# ESC-Player_BackBoardV03.net
KiCad netlist of a schematic drawn in EasyEDA Pro
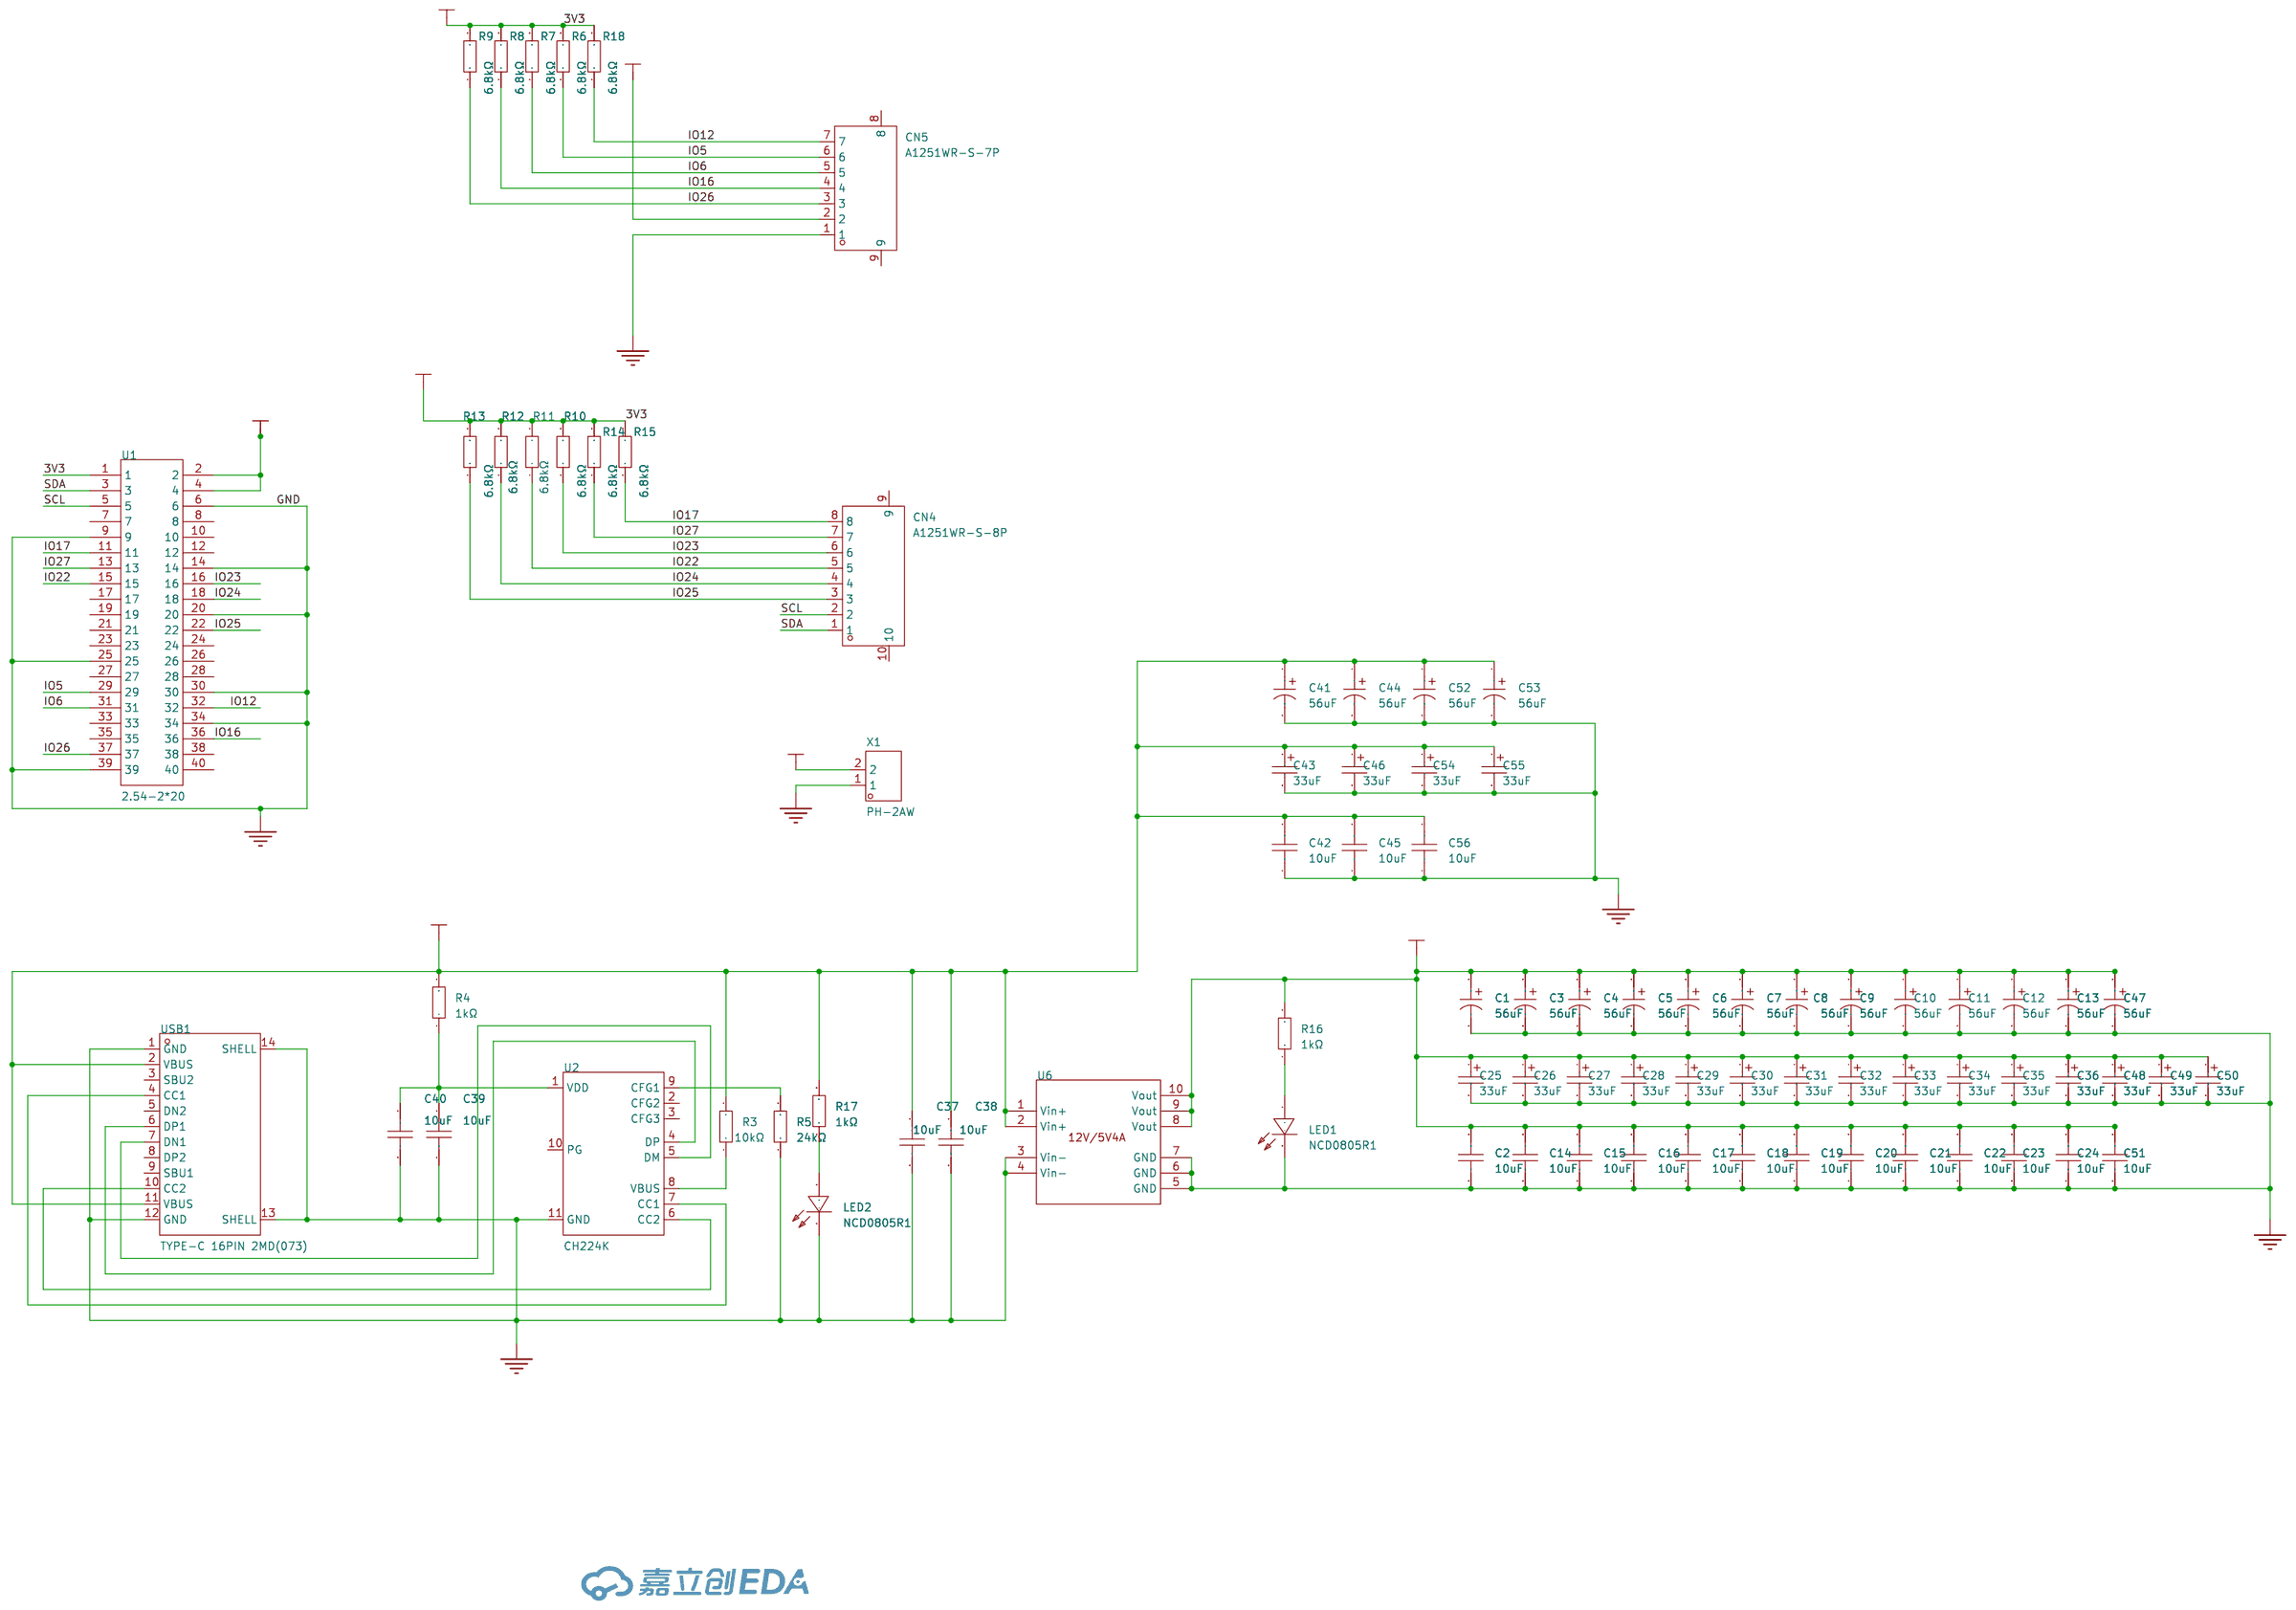
[diagram p0: schematic sheet]

(export (version "E")
  (design (tool "Eeschema 10.0.6"))
  (components
    (comp (ref "C1")
      (value "56uF")
      (footprint "easyedapro:CAP-SMD_BD6.3-L6.6-W6.6-LS7.2-FD")
      (description "容值:56uF;精度:±20%;额定电压:25V;")
      (fields (field (name "Manufacturer Part") "HBW560M1ETR-0606") (field (name "Manufacturer") "lelon(立隆)"))
      (libsource (lib "easyedapro") (part "HBW560M1ETR-0606"))
    )
    (comp (ref "C2")
      (value "10uF")
      (footprint "easyedapro:C1206")
      (description "容值:10uF;精度:±10%;额定电压:50V;材质(温度系数):X5R;")
      (fields
        (field (name "Manufacturer Part") "HGC1206R5106K500NSPJ")
        (field (name "Manufacturer") "Chinocera(华瓷)")
      )
      (libsource (lib "easyedapro") (part "HGC1206R5106K500NSPJ"))
    )
    (comp (ref "C3")
      (value "56uF")
      (footprint "easyedapro:CAP-SMD_BD6.3-L6.6-W6.6-LS7.2-FD")
      (description "容值:56uF;精度:±20%;额定电压:25V;")
      (fields (field (name "Manufacturer Part") "HBW560M1ETR-0606") (field (name "Manufacturer") "lelon(立隆)"))
      (libsource (lib "easyedapro") (part "HBW560M1ETR-0606"))
    )
    (comp (ref "C4")
      (value "56uF")
      (footprint "easyedapro:CAP-SMD_BD6.3-L6.6-W6.6-LS7.2-FD")
      (description "容值:56uF;精度:±20%;额定电压:25V;")
      (fields (field (name "Manufacturer Part") "HBW560M1ETR-0606") (field (name "Manufacturer") "lelon(立隆)"))
      (libsource (lib "easyedapro") (part "HBW560M1ETR-0606"))
    )
    (comp (ref "C5")
      (value "56uF")
      (footprint "easyedapro:CAP-SMD_BD6.3-L6.6-W6.6-LS7.2-FD")
      (description "容值:56uF;精度:±20%;额定电压:25V;")
      (fields (field (name "Manufacturer Part") "HBW560M1ETR-0606") (field (name "Manufacturer") "lelon(立隆)"))
      (libsource (lib "easyedapro") (part "HBW560M1ETR-0606"))
    )
    (comp (ref "C6")
      (value "56uF")
      (footprint "easyedapro:CAP-SMD_BD6.3-L6.6-W6.6-LS7.2-FD")
      (description "容值:56uF;精度:±20%;额定电压:25V;")
      (fields (field (name "Manufacturer Part") "HBW560M1ETR-0606") (field (name "Manufacturer") "lelon(立隆)"))
      (libsource (lib "easyedapro") (part "HBW560M1ETR-0606"))
    )
    (comp (ref "C7")
      (value "56uF")
      (footprint "easyedapro:CAP-SMD_BD6.3-L6.6-W6.6-LS7.2-FD")
      (description "容值:56uF;精度:±20%;额定电压:25V;")
      (fields (field (name "Manufacturer Part") "HBW560M1ETR-0606") (field (name "Manufacturer") "lelon(立隆)"))
      (libsource (lib "easyedapro") (part "HBW560M1ETR-0606"))
    )
    (comp (ref "C8")
      (value "56uF")
      (footprint "easyedapro:CAP-SMD_BD6.3-L6.6-W6.6-LS7.2-FD")
      (description "容值:56uF;精度:±20%;额定电压:25V;")
      (fields (field (name "Manufacturer Part") "HBW560M1ETR-0606") (field (name "Manufacturer") "lelon(立隆)"))
      (libsource (lib "easyedapro") (part "HBW560M1ETR-0606"))
    )
    (comp (ref "C9")
      (value "56uF")
      (footprint "easyedapro:CAP-SMD_BD6.3-L6.6-W6.6-LS7.2-FD")
      (description "容值:56uF;精度:±20%;额定电压:25V;")
      (fields (field (name "Manufacturer Part") "HBW560M1ETR-0606") (field (name "Manufacturer") "lelon(立隆)"))
      (libsource (lib "easyedapro") (part "HBW560M1ETR-0606"))
    )
    (comp (ref "C10")
      (value "56uF")
      (footprint "easyedapro:CAP-SMD_BD6.3-L6.6-W6.6-LS7.2-FD")
      (description "容值:56uF;精度:±20%;额定电压:25V;")
      (fields (field (name "Manufacturer Part") "HBW560M1ETR-0606") (field (name "Manufacturer") "lelon(立隆)"))
      (libsource (lib "easyedapro") (part "HBW560M1ETR-0606"))
    )
    (comp (ref "C11")
      (value "56uF")
      (footprint "easyedapro:CAP-SMD_BD6.3-L6.6-W6.6-LS7.2-FD")
      (description "容值:56uF;精度:±20%;额定电压:25V;")
      (fields (field (name "Manufacturer Part") "HBW560M1ETR-0606") (field (name "Manufacturer") "lelon(立隆)"))
      (libsource (lib "easyedapro") (part "HBW560M1ETR-0606"))
    )
    (comp (ref "C12")
      (value "56uF")
      (footprint "easyedapro:CAP-SMD_BD6.3-L6.6-W6.6-LS7.2-FD")
      (description "容值:56uF;精度:±20%;额定电压:25V;")
      (fields (field (name "Manufacturer Part") "HBW560M1ETR-0606") (field (name "Manufacturer") "lelon(立隆)"))
      (libsource (lib "easyedapro") (part "HBW560M1ETR-0606"))
    )
    (comp (ref "C13")
      (value "56uF")
      (footprint "easyedapro:CAP-SMD_BD6.3-L6.6-W6.6-LS7.2-FD")
      (description "容值:56uF;精度:±20%;额定电压:25V;")
      (fields (field (name "Manufacturer Part") "HBW560M1ETR-0606") (field (name "Manufacturer") "lelon(立隆)"))
      (libsource (lib "easyedapro") (part "HBW560M1ETR-0606"))
    )
    (comp (ref "C14")
      (value "10uF")
      (footprint "easyedapro:C1206")
      (description "容值:10uF;精度:±10%;额定电压:50V;材质(温度系数):X5R;")
      (fields
        (field (name "Manufacturer Part") "HGC1206R5106K500NSPJ")
        (field (name "Manufacturer") "Chinocera(华瓷)")
      )
      (libsource (lib "easyedapro") (part "HGC1206R5106K500NSPJ"))
    )
    (comp (ref "C15")
      (value "10uF")
      (footprint "easyedapro:C1206")
      (description "容值:10uF;精度:±10%;额定电压:50V;材质(温度系数):X5R;")
      (fields
        (field (name "Manufacturer Part") "HGC1206R5106K500NSPJ")
        (field (name "Manufacturer") "Chinocera(华瓷)")
      )
      (libsource (lib "easyedapro") (part "HGC1206R5106K500NSPJ"))
    )
    (comp (ref "C16")
      (value "10uF")
      (footprint "easyedapro:C1206")
      (description "容值:10uF;精度:±10%;额定电压:50V;材质(温度系数):X5R;")
      (fields
        (field (name "Manufacturer Part") "HGC1206R5106K500NSPJ")
        (field (name "Manufacturer") "Chinocera(华瓷)")
      )
      (libsource (lib "easyedapro") (part "HGC1206R5106K500NSPJ"))
    )
    (comp (ref "C17")
      (value "10uF")
      (footprint "easyedapro:C1206")
      (description "容值:10uF;精度:±10%;额定电压:50V;材质(温度系数):X5R;")
      (fields
        (field (name "Manufacturer Part") "HGC1206R5106K500NSPJ")
        (field (name "Manufacturer") "Chinocera(华瓷)")
      )
      (libsource (lib "easyedapro") (part "HGC1206R5106K500NSPJ"))
    )
    (comp (ref "C18")
      (value "10uF")
      (footprint "easyedapro:C1206")
      (description "容值:10uF;精度:±10%;额定电压:50V;材质(温度系数):X5R;")
      (fields
        (field (name "Manufacturer Part") "HGC1206R5106K500NSPJ")
        (field (name "Manufacturer") "Chinocera(华瓷)")
      )
      (libsource (lib "easyedapro") (part "HGC1206R5106K500NSPJ"))
    )
    (comp (ref "C19")
      (value "10uF")
      (footprint "easyedapro:C1206")
      (description "容值:10uF;精度:±10%;额定电压:50V;材质(温度系数):X5R;")
      (fields
        (field (name "Manufacturer Part") "HGC1206R5106K500NSPJ")
        (field (name "Manufacturer") "Chinocera(华瓷)")
      )
      (libsource (lib "easyedapro") (part "HGC1206R5106K500NSPJ"))
    )
    (comp (ref "C20")
      (value "10uF")
      (footprint "easyedapro:C1206")
      (description "容值:10uF;精度:±10%;额定电压:50V;材质(温度系数):X5R;")
      (fields
        (field (name "Manufacturer Part") "HGC1206R5106K500NSPJ")
        (field (name "Manufacturer") "Chinocera(华瓷)")
      )
      (libsource (lib "easyedapro") (part "HGC1206R5106K500NSPJ"))
    )
    (comp (ref "C21")
      (value "10uF")
      (footprint "easyedapro:C1206")
      (description "容值:10uF;精度:±10%;额定电压:50V;材质(温度系数):X5R;")
      (fields
        (field (name "Manufacturer Part") "HGC1206R5106K500NSPJ")
        (field (name "Manufacturer") "Chinocera(华瓷)")
      )
      (libsource (lib "easyedapro") (part "HGC1206R5106K500NSPJ"))
    )
    (comp (ref "C22")
      (value "10uF")
      (footprint "easyedapro:C1206")
      (description "容值:10uF;精度:±10%;额定电压:50V;材质(温度系数):X5R;")
      (fields
        (field (name "Manufacturer Part") "HGC1206R5106K500NSPJ")
        (field (name "Manufacturer") "Chinocera(华瓷)")
      )
      (libsource (lib "easyedapro") (part "HGC1206R5106K500NSPJ"))
    )
    (comp (ref "C23")
      (value "10uF")
      (footprint "easyedapro:C1206")
      (description "容值:10uF;精度:±10%;额定电压:50V;材质(温度系数):X5R;")
      (fields
        (field (name "Manufacturer Part") "HGC1206R5106K500NSPJ")
        (field (name "Manufacturer") "Chinocera(华瓷)")
      )
      (libsource (lib "easyedapro") (part "HGC1206R5106K500NSPJ"))
    )
    (comp (ref "C24")
      (value "10uF")
      (footprint "easyedapro:C1206")
      (description "容值:10uF;精度:±10%;额定电压:50V;材质(温度系数):X5R;")
      (fields
        (field (name "Manufacturer Part") "HGC1206R5106K500NSPJ")
        (field (name "Manufacturer") "Chinocera(华瓷)")
      )
      (libsource (lib "easyedapro") (part "HGC1206R5106K500NSPJ"))
    )
    (comp (ref "C25")
      (value "33uF")
      (footprint "easyedapro:CAP-SMD_L3.5-W2.8-R-RD")
      (description "容值:33uF;精度:±10%;额定电压:16V;等效串联电阻:2.1Ω@100kHz;")
      (fields (field (name "Manufacturer Part") "TAJB336K016RNJ") (field (name "Manufacturer") "Kyocera AVX"))
      (libsource (lib "easyedapro") (part "TAJB336K016RNJ"))
    )
    (comp (ref "C26")
      (value "33uF")
      (footprint "easyedapro:CAP-SMD_L3.5-W2.8-R-RD")
      (description "容值:33uF;精度:±10%;额定电压:16V;等效串联电阻:2.1Ω@100kHz;")
      (fields (field (name "Manufacturer Part") "TAJB336K016RNJ") (field (name "Manufacturer") "Kyocera AVX"))
      (libsource (lib "easyedapro") (part "TAJB336K016RNJ"))
    )
    (comp (ref "C27")
      (value "33uF")
      (footprint "easyedapro:CAP-SMD_L3.5-W2.8-R-RD")
      (description "容值:33uF;精度:±10%;额定电压:16V;等效串联电阻:2.1Ω@100kHz;")
      (fields (field (name "Manufacturer Part") "TAJB336K016RNJ") (field (name "Manufacturer") "Kyocera AVX"))
      (libsource (lib "easyedapro") (part "TAJB336K016RNJ"))
    )
    (comp (ref "C28")
      (value "33uF")
      (footprint "easyedapro:CAP-SMD_L3.5-W2.8-R-RD")
      (description "容值:33uF;精度:±10%;额定电压:16V;等效串联电阻:2.1Ω@100kHz;")
      (fields (field (name "Manufacturer Part") "TAJB336K016RNJ") (field (name "Manufacturer") "Kyocera AVX"))
      (libsource (lib "easyedapro") (part "TAJB336K016RNJ"))
    )
    (comp (ref "C29")
      (value "33uF")
      (footprint "easyedapro:CAP-SMD_L3.5-W2.8-R-RD")
      (description "容值:33uF;精度:±10%;额定电压:16V;等效串联电阻:2.1Ω@100kHz;")
      (fields (field (name "Manufacturer Part") "TAJB336K016RNJ") (field (name "Manufacturer") "Kyocera AVX"))
      (libsource (lib "easyedapro") (part "TAJB336K016RNJ"))
    )
    (comp (ref "C30")
      (value "33uF")
      (footprint "easyedapro:CAP-SMD_L3.5-W2.8-R-RD")
      (description "容值:33uF;精度:±10%;额定电压:16V;等效串联电阻:2.1Ω@100kHz;")
      (fields (field (name "Manufacturer Part") "TAJB336K016RNJ") (field (name "Manufacturer") "Kyocera AVX"))
      (libsource (lib "easyedapro") (part "TAJB336K016RNJ"))
    )
    (comp (ref "C31")
      (value "33uF")
      (footprint "easyedapro:CAP-SMD_L3.5-W2.8-R-RD")
      (description "容值:33uF;精度:±10%;额定电压:16V;等效串联电阻:2.1Ω@100kHz;")
      (fields (field (name "Manufacturer Part") "TAJB336K016RNJ") (field (name "Manufacturer") "Kyocera AVX"))
      (libsource (lib "easyedapro") (part "TAJB336K016RNJ"))
    )
    (comp (ref "C32")
      (value "33uF")
      (footprint "easyedapro:CAP-SMD_L3.5-W2.8-R-RD")
      (description "容值:33uF;精度:±10%;额定电压:16V;等效串联电阻:2.1Ω@100kHz;")
      (fields (field (name "Manufacturer Part") "TAJB336K016RNJ") (field (name "Manufacturer") "Kyocera AVX"))
      (libsource (lib "easyedapro") (part "TAJB336K016RNJ"))
    )
    (comp (ref "C33")
      (value "33uF")
      (footprint "easyedapro:CAP-SMD_L3.5-W2.8-R-RD")
      (description "容值:33uF;精度:±10%;额定电压:16V;等效串联电阻:2.1Ω@100kHz;")
      (fields (field (name "Manufacturer Part") "TAJB336K016RNJ") (field (name "Manufacturer") "Kyocera AVX"))
      (libsource (lib "easyedapro") (part "TAJB336K016RNJ"))
    )
    (comp (ref "C34")
      (value "33uF")
      (footprint "easyedapro:CAP-SMD_L3.5-W2.8-R-RD")
      (description "容值:33uF;精度:±10%;额定电压:16V;等效串联电阻:2.1Ω@100kHz;")
      (fields (field (name "Manufacturer Part") "TAJB336K016RNJ") (field (name "Manufacturer") "Kyocera AVX"))
      (libsource (lib "easyedapro") (part "TAJB336K016RNJ"))
    )
    (comp (ref "C35")
      (value "33uF")
      (footprint "easyedapro:CAP-SMD_L3.5-W2.8-R-RD")
      (description "容值:33uF;精度:±10%;额定电压:16V;等效串联电阻:2.1Ω@100kHz;")
      (fields (field (name "Manufacturer Part") "TAJB336K016RNJ") (field (name "Manufacturer") "Kyocera AVX"))
      (libsource (lib "easyedapro") (part "TAJB336K016RNJ"))
    )
    (comp (ref "C36")
      (value "33uF")
      (footprint "easyedapro:CAP-SMD_L3.5-W2.8-R-RD")
      (description "容值:33uF;精度:±10%;额定电压:16V;等效串联电阻:2.1Ω@100kHz;")
      (fields (field (name "Manufacturer Part") "TAJB336K016RNJ") (field (name "Manufacturer") "Kyocera AVX"))
      (libsource (lib "easyedapro") (part "TAJB336K016RNJ"))
    )
    (comp (ref "C37")
      (value "10uF")
      (footprint "easyedapro:C0805")
      (description "温度系数:X5R;额定电压:6.3V;精度:±10%;容值:10uF;")
      (fields
        (field (name "Manufacturer Part") "CL21A106KQFNNNE")
        (field (name "Manufacturer") "SAMSUNG(三星)")
      )
      (libsource (lib "easyedapro") (part "CL21A106KQFNNNE"))
    )
    (comp (ref "C38")
      (value "10uF")
      (footprint "easyedapro:C0805")
      (description "温度系数:X5R;额定电压:6.3V;精度:±10%;容值:10uF;")
      (fields
        (field (name "Manufacturer Part") "CL21A106KQFNNNE")
        (field (name "Manufacturer") "SAMSUNG(三星)")
      )
      (libsource (lib "easyedapro") (part "CL21A106KQFNNNE"))
    )
    (comp (ref "C39")
      (value "10uF")
      (footprint "easyedapro:C0805")
      (description "温度系数:X5R;额定电压:6.3V;精度:±10%;容值:10uF;")
      (fields
        (field (name "Manufacturer Part") "CL21A106KQFNNNE")
        (field (name "Manufacturer") "SAMSUNG(三星)")
      )
      (libsource (lib "easyedapro") (part "CL21A106KQFNNNE"))
    )
    (comp (ref "C40")
      (value "10uF")
      (footprint "easyedapro:C0805")
      (description "温度系数:X5R;额定电压:6.3V;精度:±10%;容值:10uF;")
      (fields
        (field (name "Manufacturer Part") "CL21A106KQFNNNE")
        (field (name "Manufacturer") "SAMSUNG(三星)")
      )
      (libsource (lib "easyedapro") (part "CL21A106KQFNNNE"))
    )
    (comp (ref "C41")
      (value "56uF")
      (footprint "easyedapro:CAP-SMD_BD6.3-L6.6-W6.6-LS7.2-FD")
      (description "容值:56uF;精度:±20%;额定电压:25V;")
      (fields (field (name "Manufacturer Part") "HBW560M1ETR-0606") (field (name "Manufacturer") "lelon(立隆)"))
      (libsource (lib "easyedapro") (part "HBW560M1ETR-0606"))
    )
    (comp (ref "C42")
      (value "10uF")
      (footprint "easyedapro:C1206")
      (description "容值:10uF;精度:±10%;额定电压:50V;材质(温度系数):X5R;")
      (fields
        (field (name "Manufacturer Part") "HGC1206R5106K500NSPJ")
        (field (name "Manufacturer") "Chinocera(华瓷)")
      )
      (libsource (lib "easyedapro") (part "HGC1206R5106K500NSPJ"))
    )
    (comp (ref "C43")
      (value "33uF")
      (footprint "easyedapro:CAP-SMD_L3.5-W2.8-R-RD")
      (description "容值:33uF;精度:±10%;额定电压:16V;等效串联电阻:2.1Ω@100kHz;")
      (fields (field (name "Manufacturer Part") "TAJB336K016RNJ") (field (name "Manufacturer") "Kyocera AVX"))
      (libsource (lib "easyedapro") (part "TAJB336K016RNJ"))
    )
    (comp (ref "C44")
      (value "56uF")
      (footprint "easyedapro:CAP-SMD_BD6.3-L6.6-W6.6-LS7.2-FD")
      (description "容值:56uF;精度:±20%;额定电压:25V;")
      (fields (field (name "Manufacturer Part") "HBW560M1ETR-0606") (field (name "Manufacturer") "lelon(立隆)"))
      (libsource (lib "easyedapro") (part "HBW560M1ETR-0606"))
    )
    (comp (ref "C45")
      (value "10uF")
      (footprint "easyedapro:C1206")
      (description "容值:10uF;精度:±10%;额定电压:50V;材质(温度系数):X5R;")
      (fields
        (field (name "Manufacturer Part") "HGC1206R5106K500NSPJ")
        (field (name "Manufacturer") "Chinocera(华瓷)")
      )
      (libsource (lib "easyedapro") (part "HGC1206R5106K500NSPJ"))
    )
    (comp (ref "C46")
      (value "33uF")
      (footprint "easyedapro:CAP-SMD_L3.5-W2.8-R-RD")
      (description "容值:33uF;精度:±10%;额定电压:16V;等效串联电阻:2.1Ω@100kHz;")
      (fields (field (name "Manufacturer Part") "TAJB336K016RNJ") (field (name "Manufacturer") "Kyocera AVX"))
      (libsource (lib "easyedapro") (part "TAJB336K016RNJ"))
    )
    (comp (ref "C47")
      (value "56uF")
      (footprint "easyedapro:CAP-SMD_BD6.3-L6.6-W6.6-LS7.2-FD")
      (description "容值:56uF;精度:±20%;额定电压:25V;")
      (fields (field (name "Manufacturer Part") "HBW560M1ETR-0606") (field (name "Manufacturer") "lelon(立隆)"))
      (libsource (lib "easyedapro") (part "HBW560M1ETR-0606"))
    )
    (comp (ref "C48")
      (value "33uF")
      (footprint "easyedapro:CAP-SMD_L3.5-W2.8-R-RD")
      (description "容值:33uF;精度:±10%;额定电压:16V;等效串联电阻:2.1Ω@100kHz;")
      (fields (field (name "Manufacturer Part") "TAJB336K016RNJ") (field (name "Manufacturer") "Kyocera AVX"))
      (libsource (lib "easyedapro") (part "TAJB336K016RNJ"))
    )
    (comp (ref "C49")
      (value "33uF")
      (footprint "easyedapro:CAP-SMD_L3.5-W2.8-R-RD")
      (description "容值:33uF;精度:±10%;额定电压:16V;等效串联电阻:2.1Ω@100kHz;")
      (fields (field (name "Manufacturer Part") "TAJB336K016RNJ") (field (name "Manufacturer") "Kyocera AVX"))
      (libsource (lib "easyedapro") (part "TAJB336K016RNJ"))
    )
    (comp (ref "C50")
      (value "33uF")
      (footprint "easyedapro:CAP-SMD_L3.5-W2.8-R-RD")
      (description "容值:33uF;精度:±10%;额定电压:16V;等效串联电阻:2.1Ω@100kHz;")
      (fields (field (name "Manufacturer Part") "TAJB336K016RNJ") (field (name "Manufacturer") "Kyocera AVX"))
      (libsource (lib "easyedapro") (part "TAJB336K016RNJ"))
    )
    (comp (ref "C51")
      (value "10uF")
      (footprint "easyedapro:C1206")
      (description "容值:10uF;精度:±10%;额定电压:50V;材质(温度系数):X5R;")
      (fields
        (field (name "Manufacturer Part") "HGC1206R5106K500NSPJ")
        (field (name "Manufacturer") "Chinocera(华瓷)")
      )
      (libsource (lib "easyedapro") (part "HGC1206R5106K500NSPJ"))
    )
    (comp (ref "C52")
      (value "56uF")
      (footprint "easyedapro:CAP-SMD_BD6.3-L6.6-W6.6-LS7.2-FD")
      (description "容值:56uF;精度:±20%;额定电压:25V;")
      (fields (field (name "Manufacturer Part") "HBW560M1ETR-0606") (field (name "Manufacturer") "lelon(立隆)"))
      (libsource (lib "easyedapro") (part "HBW560M1ETR-0606"))
    )
    (comp (ref "C53")
      (value "56uF")
      (footprint "easyedapro:CAP-SMD_BD6.3-L6.6-W6.6-LS7.2-FD")
      (description "容值:56uF;精度:±20%;额定电压:25V;")
      (fields (field (name "Manufacturer Part") "HBW560M1ETR-0606") (field (name "Manufacturer") "lelon(立隆)"))
      (libsource (lib "easyedapro") (part "HBW560M1ETR-0606"))
    )
    (comp (ref "C54")
      (value "33uF")
      (footprint "easyedapro:CAP-SMD_L3.5-W2.8-R-RD")
      (description "容值:33uF;精度:±10%;额定电压:16V;等效串联电阻:2.1Ω@100kHz;")
      (fields (field (name "Manufacturer Part") "TAJB336K016RNJ") (field (name "Manufacturer") "Kyocera AVX"))
      (libsource (lib "easyedapro") (part "TAJB336K016RNJ"))
    )
    (comp (ref "C55")
      (value "33uF")
      (footprint "easyedapro:CAP-SMD_L3.5-W2.8-R-RD")
      (description "容值:33uF;精度:±10%;额定电压:16V;等效串联电阻:2.1Ω@100kHz;")
      (fields (field (name "Manufacturer Part") "TAJB336K016RNJ") (field (name "Manufacturer") "Kyocera AVX"))
      (libsource (lib "easyedapro") (part "TAJB336K016RNJ"))
    )
    (comp (ref "C56")
      (value "10uF")
      (footprint "easyedapro:C1206")
      (description "容值:10uF;精度:±10%;额定电压:50V;材质(温度系数):X5R;")
      (fields
        (field (name "Manufacturer Part") "HGC1206R5106K500NSPJ")
        (field (name "Manufacturer") "Chinocera(华瓷)")
      )
      (libsource (lib "easyedapro") (part "HGC1206R5106K500NSPJ"))
    )
    (comp (ref "CN4")
      (value "A1251WR-S-8P")
      (footprint "easyedapro:CONN-SMD_A1251WR-S-8P")
      (description "参考系列:-;间距:1.25mm;插针结构:1x8P;排数:1;每排PIN数:8;行距:-;安装方式:-;触头材质:磷青铜;")
      (fields (field (name "Manufacturer") "CJT(长江连接器)"))
      (libsource (lib "easyedapro") (part "A1251WR-S-8P"))
    )
    (comp (ref "CN5")
      (value "A1251WR-S-7P")
      (footprint "easyedapro:CONN-SMD_A1251WR-S-7P")
      (description "参考系列:-;间距:1.25mm;插针结构:1x7P;排数:1;每排PIN数:7;行距:-;安装方式:-;触头材质:磷青铜;")
      (fields (field (name "Manufacturer") "CJT(长江连接器)"))
      (libsource (lib "easyedapro") (part "A1251WR-S-7P"))
    )
    (comp (ref "LED1")
      (value "NCD0805R1")
      (footprint "easyedapro:LED0805-R-RD")
      (fields (field (name "Manufacturer") "国星光电"))
      (libsource (lib "easyedapro") (part "FC-2012HRK-620D"))
    )
    (comp (ref "LED2")
      (value "NCD0805R1")
      (footprint "easyedapro:LED0805-R-RD")
      (fields (field (name "Manufacturer") "国星光电"))
      (libsource (lib "easyedapro") (part "FC-2012HRK-620D"))
    )
    (comp (ref "R3")
      (value "10kΩ")
      (footprint "easyedapro:R0805")
      (description "电阻类型:厚膜电阻;阻值:10kΩ;精度:±1%;功率:125mW;最大工作电压:150V;温度系数:±100ppm/°C;")
      (fields
        (field (name "Manufacturer Part") "0805W8F1002T5E")
        (field (name "Manufacturer") "UNI-ROYAL(厚声)")
      )
      (libsource (lib "easyedapro") (part "0805W8F1002T5E"))
    )
    (comp (ref "R4")
      (value "1kΩ")
      (footprint "easyedapro:R0805")
      (description "电阻类型:厚膜电阻;阻值:1kΩ;精度:±1%;功率:125mW;最大工作电压:150V;温度系数:±100ppm/°C;")
      (fields
        (field (name "Manufacturer Part") "0805W8F1001T5E")
        (field (name "Manufacturer") "UNI-ROYAL(厚声)")
      )
      (libsource (lib "easyedapro") (part "0805W8F1001T5E"))
    )
    (comp (ref "R5")
      (value "24kΩ")
      (footprint "easyedapro:R0805")
      (description "电阻类型:厚膜电阻;阻值:6.8kΩ;精度:±1%;功率:125mW;最大工作电压:150V;温度系数:±100ppm/°C;")
      (fields
        (field (name "Manufacturer Part") "0805W8F6801T5E")
        (field (name "Manufacturer") "UNI-ROYAL(厚声)")
      )
      (libsource (lib "easyedapro") (part "0805W8F6801T5E"))
    )
    (comp (ref "R6")
      (value "6.8kΩ")
      (footprint "easyedapro:R0805")
      (description "电阻类型:厚膜电阻;阻值:6.8kΩ;精度:±1%;功率:125mW;最大工作电压:150V;温度系数:±100ppm/°C;")
      (fields
        (field (name "Manufacturer Part") "0805W8F6801T5E")
        (field (name "Manufacturer") "UNI-ROYAL(厚声)")
      )
      (libsource (lib "easyedapro") (part "0805W8F6801T5E"))
    )
    (comp (ref "R7")
      (value "6.8kΩ")
      (footprint "easyedapro:R0805")
      (description "电阻类型:厚膜电阻;阻值:6.8kΩ;精度:±1%;功率:125mW;最大工作电压:150V;温度系数:±100ppm/°C;")
      (fields
        (field (name "Manufacturer Part") "0805W8F6801T5E")
        (field (name "Manufacturer") "UNI-ROYAL(厚声)")
      )
      (libsource (lib "easyedapro") (part "0805W8F6801T5E"))
    )
    (comp (ref "R8")
      (value "6.8kΩ")
      (footprint "easyedapro:R0805")
      (description "电阻类型:厚膜电阻;阻值:6.8kΩ;精度:±1%;功率:125mW;最大工作电压:150V;温度系数:±100ppm/°C;")
      (fields
        (field (name "Manufacturer Part") "0805W8F6801T5E")
        (field (name "Manufacturer") "UNI-ROYAL(厚声)")
      )
      (libsource (lib "easyedapro") (part "0805W8F6801T5E"))
    )
    (comp (ref "R9")
      (value "6.8kΩ")
      (footprint "easyedapro:R0805")
      (description "电阻类型:厚膜电阻;阻值:6.8kΩ;精度:±1%;功率:125mW;最大工作电压:150V;温度系数:±100ppm/°C;")
      (fields
        (field (name "Manufacturer Part") "0805W8F6801T5E")
        (field (name "Manufacturer") "UNI-ROYAL(厚声)")
      )
      (libsource (lib "easyedapro") (part "0805W8F6801T5E"))
    )
    (comp (ref "R10")
      (value "6.8kΩ")
      (footprint "easyedapro:R0805")
      (description "电阻类型:厚膜电阻;阻值:6.8kΩ;精度:±1%;功率:125mW;最大工作电压:150V;温度系数:±100ppm/°C;")
      (fields
        (field (name "Manufacturer Part") "0805W8F6801T5E")
        (field (name "Manufacturer") "UNI-ROYAL(厚声)")
      )
      (libsource (lib "easyedapro") (part "0805W8F6801T5E"))
    )
    (comp (ref "R11")
      (value "6.8kΩ")
      (footprint "easyedapro:R0805")
      (description "电阻类型:厚膜电阻;阻值:6.8kΩ;精度:±1%;功率:125mW;最大工作电压:150V;温度系数:±100ppm/°C;")
      (fields
        (field (name "Manufacturer Part") "0805W8F6801T5E")
        (field (name "Manufacturer") "UNI-ROYAL(厚声)")
      )
      (libsource (lib "easyedapro") (part "0805W8F6801T5E"))
    )
    (comp (ref "R12")
      (value "6.8kΩ")
      (footprint "easyedapro:R0805")
      (description "电阻类型:厚膜电阻;阻值:6.8kΩ;精度:±1%;功率:125mW;最大工作电压:150V;温度系数:±100ppm/°C;")
      (fields
        (field (name "Manufacturer Part") "0805W8F6801T5E")
        (field (name "Manufacturer") "UNI-ROYAL(厚声)")
      )
      (libsource (lib "easyedapro") (part "0805W8F6801T5E"))
    )
    (comp (ref "R13")
      (value "6.8kΩ")
      (footprint "easyedapro:R0805")
      (description "电阻类型:厚膜电阻;阻值:6.8kΩ;精度:±1%;功率:125mW;最大工作电压:150V;温度系数:±100ppm/°C;")
      (fields
        (field (name "Manufacturer Part") "0805W8F6801T5E")
        (field (name "Manufacturer") "UNI-ROYAL(厚声)")
      )
      (libsource (lib "easyedapro") (part "0805W8F6801T5E"))
    )
    (comp (ref "R14")
      (value "6.8kΩ")
      (footprint "easyedapro:R0805")
      (description "电阻类型:厚膜电阻;阻值:6.8kΩ;精度:±1%;功率:125mW;最大工作电压:150V;温度系数:±100ppm/°C;")
      (fields
        (field (name "Manufacturer Part") "0805W8F6801T5E")
        (field (name "Manufacturer") "UNI-ROYAL(厚声)")
      )
      (libsource (lib "easyedapro") (part "0805W8F6801T5E"))
    )
    (comp (ref "R15")
      (value "6.8kΩ")
      (footprint "easyedapro:R0805")
      (description "电阻类型:厚膜电阻;阻值:6.8kΩ;精度:±1%;功率:125mW;最大工作电压:150V;温度系数:±100ppm/°C;")
      (fields
        (field (name "Manufacturer Part") "0805W8F6801T5E")
        (field (name "Manufacturer") "UNI-ROYAL(厚声)")
      )
      (libsource (lib "easyedapro") (part "0805W8F6801T5E"))
    )
    (comp (ref "R16")
      (value "1kΩ")
      (footprint "easyedapro:R0805")
      (description "电阻类型:厚膜电阻;阻值:1kΩ;精度:±1%;功率:125mW;最大工作电压:150V;温度系数:±100ppm/°C;")
      (fields
        (field (name "Manufacturer Part") "0805W8F1001T5E")
        (field (name "Manufacturer") "UNI-ROYAL(厚声)")
      )
      (libsource (lib "easyedapro") (part "0805W8F1001T5E"))
    )
    (comp (ref "R17")
      (value "1kΩ")
      (footprint "easyedapro:R0805")
      (description "电阻类型:厚膜电阻;阻值:1kΩ;精度:±1%;功率:125mW;最大工作电压:150V;温度系数:±100ppm/°C;")
      (fields
        (field (name "Manufacturer Part") "0805W8F1001T5E")
        (field (name "Manufacturer") "UNI-ROYAL(厚声)")
      )
      (libsource (lib "easyedapro") (part "0805W8F1001T5E"))
    )
    (comp (ref "R18")
      (value "6.8kΩ")
      (footprint "easyedapro:R0805")
      (description "电阻类型:厚膜电阻;阻值:6.8kΩ;精度:±1%;功率:125mW;最大工作电压:150V;温度系数:±100ppm/°C;")
      (fields
        (field (name "Manufacturer Part") "0805W8F6801T5E")
        (field (name "Manufacturer") "UNI-ROYAL(厚声)")
      )
      (libsource (lib "easyedapro") (part "0805W8F6801T5E"))
    )
    (comp (ref "U1")
      (value "2.54-2*20")
      (footprint "easyedapro:HDR-TH_40P-P2.54-V-F-R2-C20-S2.54")
      (fields (field (name "Manufacturer") "ZHOURI(洲日)"))
      (libsource (lib "easyedapro") (part "2.54-2*20"))
    )
    (comp (ref "U2")
      (value "CH224K")
      (footprint "easyedapro:ESSOP-10_L4.9-W3.9-P1.0-LS6.0-TL-EP")
      (fields (field (name "Manufacturer") "WCH(南京沁恒)"))
      (libsource (lib "easyedapro") (part "CH224K"))
    )
    (comp (ref "U6") (value "~") (footprint "easyedapro:dcdc") (libsource (lib "easyedapro") (part "dcdc")))
    (comp (ref "USB1")
      (value "TYPE-C 16PIN 2MD(073)")
      (footprint "easyedapro:USB-C-SMD_TYPE-C-6PIN-2MD-073")
      (description "连接器类型:Type-C;标准:USB 3.1;公母:母;安装方式:卧贴;触点数量:16P;端口数量:1;额定电流 - 电源:5A;工作温度范围:-25°C~+85°C;")
      (fields (field (name "Manufacturer") "SHOU HAN(首韩)"))
      (libsource (lib "easyedapro") (part "TYPE-C 16PIN 2MD(073)"))
    )
    (comp (ref "X1")
      (value "PH-2AW")
      (footprint "easyedapro:CONN-TH_2P-P2.00_PH-2AW")
      (description "参考系列:PH;间距:2mm;插针结构:1x2P;排数:1;每排PIN数:2;行距:-;安装方式:-;触头材质:-;")
      (fields (field (name "Manufacturer") "BOOMELE(博穆精密)"))
      (libsource (lib "easyedapro") (part "PH-2AW RHOS"))
    )
  )
  (nets
    (net (code "1") (name "/IO5") (class "Default")
      (node (ref "CN5") (pin "6") (pinfunction "6_6") (pintype "input"))
      (node (ref "R6") (pin "1") (pinfunction "1_1") (pintype "input"))
      (node (ref "U1") (pin "29") (pinfunction "29_29") (pintype "unspecified"))
    )
    (net (code "2") (name "/IO6") (class "Default")
      (node (ref "CN5") (pin "5") (pinfunction "5_5") (pintype "input"))
      (node (ref "R7") (pin "1") (pinfunction "1_1") (pintype "input"))
      (node (ref "U1") (pin "31") (pinfunction "31_31") (pintype "unspecified"))
    )
    (net (code "3") (name "/IO12") (class "Default")
      (node (ref "CN5") (pin "7") (pinfunction "7_7") (pintype "input"))
      (node (ref "R18") (pin "1") (pinfunction "1_1") (pintype "input"))
      (node (ref "U1") (pin "32") (pinfunction "32_32") (pintype "unspecified"))
    )
    (net (code "4") (name "/IO16") (class "Default")
      (node (ref "CN5") (pin "4") (pinfunction "4_4") (pintype "input"))
      (node (ref "R8") (pin "1") (pinfunction "1_1") (pintype "input"))
      (node (ref "U1") (pin "36") (pinfunction "36_36") (pintype "unspecified"))
    )
    (net (code "5") (name "/IO17") (class "Default")
      (node (ref "CN4") (pin "8") (pinfunction "8_8") (pintype "input"))
      (node (ref "R15") (pin "1") (pinfunction "1_1") (pintype "input"))
      (node (ref "U1") (pin "11") (pinfunction "11_11") (pintype "unspecified"))
    )
    (net (code "6") (name "/IO22") (class "Default")
      (node (ref "CN4") (pin "5") (pinfunction "5_5") (pintype "input"))
      (node (ref "R11") (pin "1") (pinfunction "1_1") (pintype "input"))
      (node (ref "U1") (pin "15") (pinfunction "15_15") (pintype "unspecified"))
    )
    (net (code "7") (name "/IO23") (class "Default")
      (node (ref "CN4") (pin "6") (pinfunction "6_6") (pintype "input"))
      (node (ref "R10") (pin "1") (pinfunction "1_1") (pintype "input"))
      (node (ref "U1") (pin "16") (pinfunction "16_16") (pintype "unspecified"))
    )
    (net (code "8") (name "/IO24") (class "Default")
      (node (ref "CN4") (pin "4") (pinfunction "4_4") (pintype "input"))
      (node (ref "R12") (pin "1") (pinfunction "1_1") (pintype "input"))
      (node (ref "U1") (pin "18") (pinfunction "18_18") (pintype "unspecified"))
    )
    (net (code "9") (name "/IO25") (class "Default")
      (node (ref "CN4") (pin "3") (pinfunction "3_3") (pintype "input"))
      (node (ref "R13") (pin "1") (pinfunction "1_1") (pintype "input"))
      (node (ref "U1") (pin "22") (pinfunction "22_22") (pintype "unspecified"))
    )
    (net (code "10") (name "/IO26") (class "Default")
      (node (ref "CN5") (pin "3") (pinfunction "3_3") (pintype "input"))
      (node (ref "R9") (pin "1") (pinfunction "1_1") (pintype "input"))
      (node (ref "U1") (pin "37") (pinfunction "37_37") (pintype "unspecified"))
    )
    (net (code "11") (name "/IO27") (class "Default")
      (node (ref "CN4") (pin "7") (pinfunction "7_7") (pintype "input"))
      (node (ref "R14") (pin "1") (pinfunction "1_1") (pintype "input"))
      (node (ref "U1") (pin "13") (pinfunction "13_13") (pintype "unspecified"))
    )
    (net (code "12") (name "/SCL") (class "Default")
      (node (ref "CN4") (pin "2") (pinfunction "2_2") (pintype "input"))
      (node (ref "U1") (pin "5") (pinfunction "5_5") (pintype "unspecified"))
    )
    (net (code "13") (name "/SDA") (class "Default")
      (node (ref "CN4") (pin "1") (pinfunction "1_1") (pintype "input"))
      (node (ref "U1") (pin "3") (pinfunction "3_3") (pintype "unspecified"))
    )
    (net (code "14") (name "3V3") (class "Default")
      (node (ref "R10") (pin "2") (pinfunction "2_2") (pintype "input"))
      (node (ref "R11") (pin "2") (pinfunction "2_2") (pintype "input"))
      (node (ref "R12") (pin "2") (pinfunction "2_2") (pintype "input"))
      (node (ref "R13") (pin "2") (pinfunction "2_2") (pintype "input"))
      (node (ref "R14") (pin "2") (pinfunction "2_2") (pintype "input"))
      (node (ref "R15") (pin "2") (pinfunction "2_2") (pintype "input"))
      (node (ref "R18") (pin "2") (pinfunction "2_2") (pintype "input"))
      (node (ref "R6") (pin "2") (pinfunction "2_2") (pintype "input"))
      (node (ref "R7") (pin "2") (pinfunction "2_2") (pintype "input"))
      (node (ref "R8") (pin "2") (pinfunction "2_2") (pintype "input"))
      (node (ref "R9") (pin "2") (pinfunction "2_2") (pintype "input"))
      (node (ref "U1") (pin "1") (pinfunction "1_1") (pintype "unspecified"))
    )
    (net (code "15") (name "5V") (class "Default")
      (node (ref "C1") (pin "1") (pinfunction "1_1") (pintype "input"))
      (node (ref "C10") (pin "1") (pinfunction "1_1") (pintype "input"))
      (node (ref "C11") (pin "1") (pinfunction "1_1") (pintype "input"))
      (node (ref "C12") (pin "1") (pinfunction "1_1") (pintype "input"))
      (node (ref "C13") (pin "1") (pinfunction "1_1") (pintype "input"))
      (node (ref "C14") (pin "2") (pinfunction "2_2") (pintype "unspecified"))
      (node (ref "C15") (pin "2") (pinfunction "2_2") (pintype "unspecified"))
      (node (ref "C16") (pin "2") (pinfunction "2_2") (pintype "unspecified"))
      (node (ref "C17") (pin "2") (pinfunction "2_2") (pintype "unspecified"))
      (node (ref "C18") (pin "2") (pinfunction "2_2") (pintype "unspecified"))
      (node (ref "C19") (pin "2") (pinfunction "2_2") (pintype "unspecified"))
      (node (ref "C2") (pin "2") (pinfunction "2_2") (pintype "unspecified"))
      (node (ref "C20") (pin "2") (pinfunction "2_2") (pintype "unspecified"))
      (node (ref "C21") (pin "2") (pinfunction "2_2") (pintype "unspecified"))
      (node (ref "C22") (pin "2") (pinfunction "2_2") (pintype "unspecified"))
      (node (ref "C23") (pin "2") (pinfunction "2_2") (pintype "unspecified"))
      (node (ref "C24") (pin "2") (pinfunction "2_2") (pintype "unspecified"))
      (node (ref "C25") (pin "1") (pinfunction "1_1") (pintype "input"))
      (node (ref "C26") (pin "1") (pinfunction "1_1") (pintype "input"))
      (node (ref "C27") (pin "1") (pinfunction "1_1") (pintype "input"))
      (node (ref "C28") (pin "1") (pinfunction "1_1") (pintype "input"))
      (node (ref "C29") (pin "1") (pinfunction "1_1") (pintype "input"))
      (node (ref "C3") (pin "1") (pinfunction "1_1") (pintype "input"))
      (node (ref "C30") (pin "1") (pinfunction "1_1") (pintype "input"))
      (node (ref "C31") (pin "1") (pinfunction "1_1") (pintype "input"))
      (node (ref "C32") (pin "1") (pinfunction "1_1") (pintype "input"))
      (node (ref "C33") (pin "1") (pinfunction "1_1") (pintype "input"))
      (node (ref "C34") (pin "1") (pinfunction "1_1") (pintype "input"))
      (node (ref "C35") (pin "1") (pinfunction "1_1") (pintype "input"))
      (node (ref "C36") (pin "1") (pinfunction "1_1") (pintype "input"))
      (node (ref "C4") (pin "1") (pinfunction "1_1") (pintype "input"))
      (node (ref "C47") (pin "1") (pinfunction "1_1") (pintype "input"))
      (node (ref "C48") (pin "1") (pinfunction "1_1") (pintype "input"))
      (node (ref "C49") (pin "1") (pinfunction "1_1") (pintype "input"))
      (node (ref "C5") (pin "1") (pinfunction "1_1") (pintype "input"))
      (node (ref "C50") (pin "1") (pinfunction "1_1") (pintype "input"))
      (node (ref "C51") (pin "2") (pinfunction "2_2") (pintype "unspecified"))
      (node (ref "C6") (pin "1") (pinfunction "1_1") (pintype "input"))
      (node (ref "C7") (pin "1") (pinfunction "1_1") (pintype "input"))
      (node (ref "C8") (pin "1") (pinfunction "1_1") (pintype "input"))
      (node (ref "C9") (pin "1") (pinfunction "1_1") (pintype "input"))
      (node (ref "CN5") (pin "2") (pinfunction "2_2") (pintype "input"))
      (node (ref "R16") (pin "2") (pinfunction "2_2") (pintype "input"))
      (node (ref "U1") (pin "2") (pinfunction "2_2") (pintype "unspecified"))
      (node (ref "U1") (pin "4") (pinfunction "4_4") (pintype "unspecified"))
      (node (ref "U6") (pin "10") (pinfunction "Vout_10") (pintype "input"))
      (node (ref "U6") (pin "8") (pinfunction "Vout_8") (pintype "input"))
      (node (ref "U6") (pin "9") (pinfunction "Vout_9") (pintype "input"))
    )
    (net (code "16") (name "GND") (class "Default")
      (node (ref "C1") (pin "2") (pinfunction "2_2") (pintype "input"))
      (node (ref "C10") (pin "2") (pinfunction "2_2") (pintype "input"))
      (node (ref "C11") (pin "2") (pinfunction "2_2") (pintype "input"))
      (node (ref "C12") (pin "2") (pinfunction "2_2") (pintype "input"))
      (node (ref "C13") (pin "2") (pinfunction "2_2") (pintype "input"))
      (node (ref "C14") (pin "1") (pinfunction "1_1") (pintype "unspecified"))
      (node (ref "C15") (pin "1") (pinfunction "1_1") (pintype "unspecified"))
      (node (ref "C16") (pin "1") (pinfunction "1_1") (pintype "unspecified"))
      (node (ref "C17") (pin "1") (pinfunction "1_1") (pintype "unspecified"))
      (node (ref "C18") (pin "1") (pinfunction "1_1") (pintype "unspecified"))
      (node (ref "C19") (pin "1") (pinfunction "1_1") (pintype "unspecified"))
      (node (ref "C2") (pin "1") (pinfunction "1_1") (pintype "unspecified"))
      (node (ref "C20") (pin "1") (pinfunction "1_1") (pintype "unspecified"))
      (node (ref "C21") (pin "1") (pinfunction "1_1") (pintype "unspecified"))
      (node (ref "C22") (pin "1") (pinfunction "1_1") (pintype "unspecified"))
      (node (ref "C23") (pin "1") (pinfunction "1_1") (pintype "unspecified"))
      (node (ref "C24") (pin "1") (pinfunction "1_1") (pintype "unspecified"))
      (node (ref "C25") (pin "2") (pinfunction "2_2") (pintype "input"))
      (node (ref "C26") (pin "2") (pinfunction "2_2") (pintype "input"))
      (node (ref "C27") (pin "2") (pinfunction "2_2") (pintype "input"))
      (node (ref "C28") (pin "2") (pinfunction "2_2") (pintype "input"))
      (node (ref "C29") (pin "2") (pinfunction "2_2") (pintype "input"))
      (node (ref "C3") (pin "2") (pinfunction "2_2") (pintype "input"))
      (node (ref "C30") (pin "2") (pinfunction "2_2") (pintype "input"))
      (node (ref "C31") (pin "2") (pinfunction "2_2") (pintype "input"))
      (node (ref "C32") (pin "2") (pinfunction "2_2") (pintype "input"))
      (node (ref "C33") (pin "2") (pinfunction "2_2") (pintype "input"))
      (node (ref "C34") (pin "2") (pinfunction "2_2") (pintype "input"))
      (node (ref "C35") (pin "2") (pinfunction "2_2") (pintype "input"))
      (node (ref "C36") (pin "2") (pinfunction "2_2") (pintype "input"))
      (node (ref "C37") (pin "2") (pinfunction "2_2") (pintype "input"))
      (node (ref "C38") (pin "2") (pinfunction "2_2") (pintype "input"))
      (node (ref "C39") (pin "2") (pinfunction "2_2") (pintype "input"))
      (node (ref "C4") (pin "2") (pinfunction "2_2") (pintype "input"))
      (node (ref "C40") (pin "2") (pinfunction "2_2") (pintype "input"))
      (node (ref "C41") (pin "2") (pinfunction "2_2") (pintype "input"))
      (node (ref "C42") (pin "1") (pinfunction "1_1") (pintype "unspecified"))
      (node (ref "C43") (pin "2") (pinfunction "2_2") (pintype "input"))
      (node (ref "C44") (pin "2") (pinfunction "2_2") (pintype "input"))
      (node (ref "C45") (pin "1") (pinfunction "1_1") (pintype "unspecified"))
      (node (ref "C46") (pin "2") (pinfunction "2_2") (pintype "input"))
      (node (ref "C47") (pin "2") (pinfunction "2_2") (pintype "input"))
      (node (ref "C48") (pin "2") (pinfunction "2_2") (pintype "input"))
      (node (ref "C49") (pin "2") (pinfunction "2_2") (pintype "input"))
      (node (ref "C5") (pin "2") (pinfunction "2_2") (pintype "input"))
      (node (ref "C50") (pin "2") (pinfunction "2_2") (pintype "input"))
      (node (ref "C51") (pin "1") (pinfunction "1_1") (pintype "unspecified"))
      (node (ref "C52") (pin "2") (pinfunction "2_2") (pintype "input"))
      (node (ref "C53") (pin "2") (pinfunction "2_2") (pintype "input"))
      (node (ref "C54") (pin "2") (pinfunction "2_2") (pintype "input"))
      (node (ref "C55") (pin "2") (pinfunction "2_2") (pintype "input"))
      (node (ref "C56") (pin "1") (pinfunction "1_1") (pintype "unspecified"))
      (node (ref "C6") (pin "2") (pinfunction "2_2") (pintype "input"))
      (node (ref "C7") (pin "2") (pinfunction "2_2") (pintype "input"))
      (node (ref "C8") (pin "2") (pinfunction "2_2") (pintype "input"))
      (node (ref "C9") (pin "2") (pinfunction "2_2") (pintype "input"))
      (node (ref "CN5") (pin "1") (pinfunction "1_1") (pintype "input"))
      (node (ref "LED1") (pin "2") (pinfunction "-_2") (pintype "unspecified"))
      (node (ref "LED2") (pin "2") (pinfunction "-_2") (pintype "unspecified"))
      (node (ref "R5") (pin "1") (pinfunction "1_1") (pintype "input"))
      (node (ref "U1") (pin "14") (pinfunction "14_14") (pintype "unspecified"))
      (node (ref "U1") (pin "20") (pinfunction "20_20") (pintype "unspecified"))
      (node (ref "U1") (pin "25") (pinfunction "25_25") (pintype "unspecified"))
      (node (ref "U1") (pin "30") (pinfunction "30_30") (pintype "unspecified"))
      (node (ref "U1") (pin "34") (pinfunction "34_34") (pintype "unspecified"))
      (node (ref "U1") (pin "39") (pinfunction "39_39") (pintype "unspecified"))
      (node (ref "U1") (pin "6") (pinfunction "6_6") (pintype "unspecified"))
      (node (ref "U1") (pin "9") (pinfunction "9_9") (pintype "unspecified"))
      (node (ref "U2") (pin "11") (pinfunction "GND_11") (pintype "unspecified"))
      (node (ref "U6") (pin "3") (pinfunction "Vin-_3") (pintype "input"))
      (node (ref "U6") (pin "4") (pinfunction "Vin-_4") (pintype "input"))
      (node (ref "U6") (pin "5") (pinfunction "GND_5") (pintype "input"))
      (node (ref "U6") (pin "6") (pinfunction "GND_6") (pintype "input"))
      (node (ref "U6") (pin "7") (pinfunction "GND_7") (pintype "input"))
      (node (ref "USB1") (pin "1") (pinfunction "GND_1") (pintype "unspecified"))
      (node (ref "USB1") (pin "12") (pinfunction "GND_12") (pintype "unspecified"))
      (node (ref "USB1") (pin "13") (pinfunction "SHELL_13") (pintype "unspecified"))
      (node (ref "USB1") (pin "14") (pinfunction "SHELL_14") (pintype "unspecified"))
      (node (ref "X1") (pin "1") (pinfunction "1_1") (pintype "input"))
    )
    (net (code "17") (name "Net-(LED1-+)") (class "Default")
      (node (ref "LED1") (pin "1") (pinfunction "+_1") (pintype "unspecified"))
      (node (ref "R16") (pin "1") (pinfunction "1_1") (pintype "input"))
    )
    (net (code "18") (name "Net-(LED2-+)") (class "Default")
      (node (ref "LED2") (pin "1") (pinfunction "+_1") (pintype "unspecified"))
      (node (ref "R17") (pin "1") (pinfunction "1_1") (pintype "input"))
    )
    (net (code "19") (name "Net-(U2-CC1)") (class "Default")
      (node (ref "U2") (pin "7") (pinfunction "CC1_7") (pintype "unspecified"))
      (node (ref "USB1") (pin "4") (pinfunction "CC1_4") (pintype "unspecified"))
    )
    (net (code "20") (name "Net-(U2-CC2)") (class "Default")
      (node (ref "U2") (pin "6") (pinfunction "CC2_6") (pintype "unspecified"))
      (node (ref "USB1") (pin "10") (pinfunction "CC2_10") (pintype "unspecified"))
    )
    (net (code "21") (name "Net-(U2-CFG1)") (class "Default")
      (node (ref "R5") (pin "2") (pinfunction "2_2") (pintype "input"))
      (node (ref "U2") (pin "9") (pinfunction "CFG1_9") (pintype "unspecified"))
    )
    (net (code "22") (name "Net-(U2-DM)") (class "Default")
      (node (ref "U2") (pin "5") (pinfunction "DM_5") (pintype "unspecified"))
      (node (ref "USB1") (pin "7") (pinfunction "DN1_7") (pintype "unspecified"))
    )
    (net (code "23") (name "Net-(U2-DP)") (class "Default")
      (node (ref "U2") (pin "4") (pinfunction "DP_4") (pintype "unspecified"))
      (node (ref "USB1") (pin "6") (pinfunction "DP1_6") (pintype "unspecified"))
    )
    (net (code "24") (name "Net-(U2-VBUS)") (class "Default")
      (node (ref "R3") (pin "1") (pinfunction "1_1") (pintype "input"))
      (node (ref "U2") (pin "8") (pinfunction "VBUS_8") (pintype "unspecified"))
    )
    (net (code "25") (name "Net-(U2-VDD)") (class "Default")
      (node (ref "C39") (pin "1") (pinfunction "1_1") (pintype "input"))
      (node (ref "C40") (pin "1") (pinfunction "1_1") (pintype "input"))
      (node (ref "R4") (pin "1") (pinfunction "1_1") (pintype "input"))
      (node (ref "U2") (pin "1") (pinfunction "VDD_1") (pintype "unspecified"))
    )
    (net (code "26") (name "VBUS") (class "Default")
      (node (ref "C37") (pin "1") (pinfunction "1_1") (pintype "input"))
      (node (ref "C38") (pin "1") (pinfunction "1_1") (pintype "input"))
      (node (ref "C41") (pin "1") (pinfunction "1_1") (pintype "input"))
      (node (ref "C42") (pin "2") (pinfunction "2_2") (pintype "unspecified"))
      (node (ref "C43") (pin "1") (pinfunction "1_1") (pintype "input"))
      (node (ref "C44") (pin "1") (pinfunction "1_1") (pintype "input"))
      (node (ref "C45") (pin "2") (pinfunction "2_2") (pintype "unspecified"))
      (node (ref "C46") (pin "1") (pinfunction "1_1") (pintype "input"))
      (node (ref "C52") (pin "1") (pinfunction "1_1") (pintype "input"))
      (node (ref "C53") (pin "1") (pinfunction "1_1") (pintype "input"))
      (node (ref "C54") (pin "1") (pinfunction "1_1") (pintype "input"))
      (node (ref "C55") (pin "1") (pinfunction "1_1") (pintype "input"))
      (node (ref "C56") (pin "2") (pinfunction "2_2") (pintype "unspecified"))
      (node (ref "R17") (pin "2") (pinfunction "2_2") (pintype "input"))
      (node (ref "R3") (pin "2") (pinfunction "2_2") (pintype "input"))
      (node (ref "R4") (pin "2") (pinfunction "2_2") (pintype "input"))
      (node (ref "U6") (pin "1") (pinfunction "Vin+_1") (pintype "input"))
      (node (ref "U6") (pin "2") (pinfunction "Vin+_2") (pintype "input"))
      (node (ref "USB1") (pin "11") (pinfunction "VBUS_11") (pintype "unspecified"))
      (node (ref "USB1") (pin "2") (pinfunction "VBUS_2") (pintype "unspecified"))
      (node (ref "X1") (pin "2") (pinfunction "2_2") (pintype "input"))
    )
    (net (code "27") (name "unconnected-(CN4-Pad9)") (class "Default")
      (node (ref "CN4") (pin "9") (pinfunction "9_9") (pintype "input"))
    )
    (net (code "28") (name "unconnected-(CN4-Pad10)") (class "Default")
      (node (ref "CN4") (pin "10") (pinfunction "10_10") (pintype "input"))
    )
    (net (code "29") (name "unconnected-(CN5-Pad8)") (class "Default")
      (node (ref "CN5") (pin "8") (pinfunction "8_8") (pintype "input"))
    )
    (net (code "30") (name "unconnected-(CN5-Pad9)") (class "Default")
      (node (ref "CN5") (pin "9") (pinfunction "9_9") (pintype "input"))
    )
    (net (code "31") (name "unconnected-(U1-Pad7)") (class "Default")
      (node (ref "U1") (pin "7") (pinfunction "7_7") (pintype "unspecified"))
    )
    (net (code "32") (name "unconnected-(U1-Pad8)") (class "Default")
      (node (ref "U1") (pin "8") (pinfunction "8_8") (pintype "unspecified"))
    )
    (net (code "33") (name "unconnected-(U1-Pad10)") (class "Default")
      (node (ref "U1") (pin "10") (pinfunction "10_10") (pintype "unspecified"))
    )
    (net (code "34") (name "unconnected-(U1-Pad12)") (class "Default")
      (node (ref "U1") (pin "12") (pinfunction "12_12") (pintype "unspecified"))
    )
    (net (code "35") (name "unconnected-(U1-Pad17)") (class "Default")
      (node (ref "U1") (pin "17") (pinfunction "17_17") (pintype "unspecified"))
    )
    (net (code "36") (name "unconnected-(U1-Pad19)") (class "Default")
      (node (ref "U1") (pin "19") (pinfunction "19_19") (pintype "unspecified"))
    )
    (net (code "37") (name "unconnected-(U1-Pad21)") (class "Default")
      (node (ref "U1") (pin "21") (pinfunction "21_21") (pintype "unspecified"))
    )
    (net (code "38") (name "unconnected-(U1-Pad23)") (class "Default")
      (node (ref "U1") (pin "23") (pinfunction "23_23") (pintype "unspecified"))
    )
    (net (code "39") (name "unconnected-(U1-Pad24)") (class "Default")
      (node (ref "U1") (pin "24") (pinfunction "24_24") (pintype "unspecified"))
    )
    (net (code "40") (name "unconnected-(U1-Pad26)") (class "Default")
      (node (ref "U1") (pin "26") (pinfunction "26_26") (pintype "unspecified"))
    )
    (net (code "41") (name "unconnected-(U1-Pad27)") (class "Default")
      (node (ref "U1") (pin "27") (pinfunction "27_27") (pintype "unspecified"))
    )
    (net (code "42") (name "unconnected-(U1-Pad28)") (class "Default")
      (node (ref "U1") (pin "28") (pinfunction "28_28") (pintype "unspecified"))
    )
    (net (code "43") (name "unconnected-(U1-Pad33)") (class "Default")
      (node (ref "U1") (pin "33") (pinfunction "33_33") (pintype "unspecified"))
    )
    (net (code "44") (name "unconnected-(U1-Pad35)") (class "Default")
      (node (ref "U1") (pin "35") (pinfunction "35_35") (pintype "unspecified"))
    )
    (net (code "45") (name "unconnected-(U1-Pad38)") (class "Default")
      (node (ref "U1") (pin "38") (pinfunction "38_38") (pintype "unspecified"))
    )
    (net (code "46") (name "unconnected-(U1-Pad40)") (class "Default")
      (node (ref "U1") (pin "40") (pinfunction "40_40") (pintype "unspecified"))
    )
    (net (code "47") (name "unconnected-(U2-CFG2-Pad2)") (class "Default")
      (node (ref "U2") (pin "2") (pinfunction "CFG2_2") (pintype "unspecified"))
    )
    (net (code "48") (name "unconnected-(U2-CFG3-Pad3)") (class "Default")
      (node (ref "U2") (pin "3") (pinfunction "CFG3_3") (pintype "unspecified"))
    )
    (net (code "49") (name "unconnected-(U2-PG-Pad10)") (class "Default")
      (node (ref "U2") (pin "10") (pinfunction "PG_10") (pintype "unspecified"))
    )
    (net (code "50") (name "unconnected-(USB1-DN2-Pad5)") (class "Default")
      (node (ref "USB1") (pin "5") (pinfunction "DN2_5") (pintype "unspecified"))
    )
    (net (code "51") (name "unconnected-(USB1-DP2-Pad8)") (class "Default")
      (node (ref "USB1") (pin "8") (pinfunction "DP2_8") (pintype "unspecified"))
    )
    (net (code "52") (name "unconnected-(USB1-SBU1-Pad9)") (class "Default")
      (node (ref "USB1") (pin "9") (pinfunction "SBU1_9") (pintype "unspecified"))
    )
    (net (code "53") (name "unconnected-(USB1-SBU2-Pad3)") (class "Default")
      (node (ref "USB1") (pin "3") (pinfunction "SBU2_3") (pintype "unspecified"))
    )
  )
)
